# CrazyPong.net
KiCad netlist of a schematic drawn in EAGLE
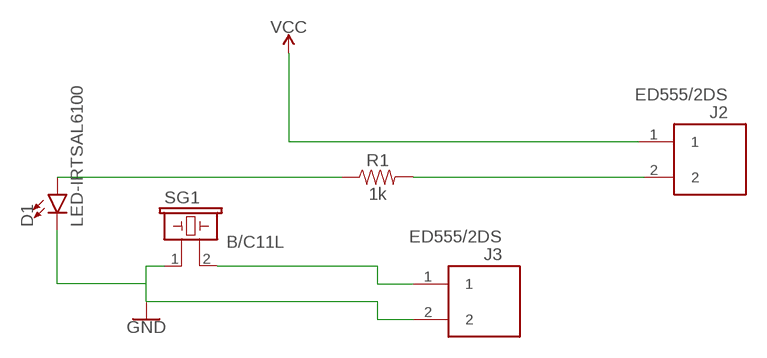
[diagram p0: schematic, sheet 1]

(export (version "E")
  (design (tool "Eeschema 10.0.6"))
  (components
    (comp (ref "D1")
      (value "LED-IRTSAL6100")
      (footprint "eagle-import:LED_5MM")
      (libsource (lib "eagle-import") (part "LED-IRTSAL6100"))
    )
    (comp (ref "J2")
      (value "ED555/2DS")
      (footprint "eagle-import:ED555_2DS")
      (libsource (lib "eagle-import") (part "ED555/2DS"))
    )
    (comp (ref "J3")
      (value "ED555/2DS")
      (footprint "eagle-import:ED555_2DS")
      (libsource (lib "eagle-import") (part "ED555/2DS"))
    )
    (comp (ref "R1")
      (value "1k")
      (footprint "eagle-import:AXIAL-0.3-KIT")
      (libsource (lib "eagle-import") (part "1KOHM-HORIZ_KIT-1/4W-1%"))
    )
    (comp (ref "SG1")
      (value "B/C11L")
      (footprint "eagle-import:B_C11L")
      (libsource (lib "eagle-import") (part "B/C11L"))
    )
  )
  (nets
    (net (code "1") (name "GND") (class "Default")
      (node (ref "D1") (pin "K") (pinfunction "C_K") (pintype "passive"))
      (node (ref "J3") (pin "2") (pinfunction "2_2") (pintype "bidirectional"))
      (node (ref "SG1") (pin "1") (pinfunction "1_1") (pintype "passive"))
    )
    (net (code "2") (name "Net-(J3-Pad1)") (class "Default")
      (node (ref "J3") (pin "1") (pinfunction "1_1") (pintype "bidirectional"))
      (node (ref "SG1") (pin "2") (pinfunction "2_2") (pintype "passive"))
    )
    (net (code "3") (name "Net-(R1-1)") (class "Default")
      (node (ref "D1") (pin "A") (pinfunction "A_A") (pintype "passive"))
      (node (ref "R1") (pin "P$1") (pinfunction "1_P$1") (pintype "passive"))
    )
    (net (code "4") (name "VCC") (class "Default")
      (node (ref "J2") (pin "1") (pinfunction "1_1") (pintype "bidirectional"))
    )
    (net (code "5") (name "unconnected-(J2-Pad2)") (class "Default")
      (node (ref "J2") (pin "2") (pinfunction "2_2") (pintype "bidirectional"))
    )
    (net (code "6") (name "unconnected-(R1-2-PadP$2)") (class "Default")
      (node (ref "R1") (pin "P$2") (pinfunction "2_P$2") (pintype "passive"))
    )
  )
)
